# LM22674-5_0.net
KiCad netlist of a schematic drawn in EAGLE
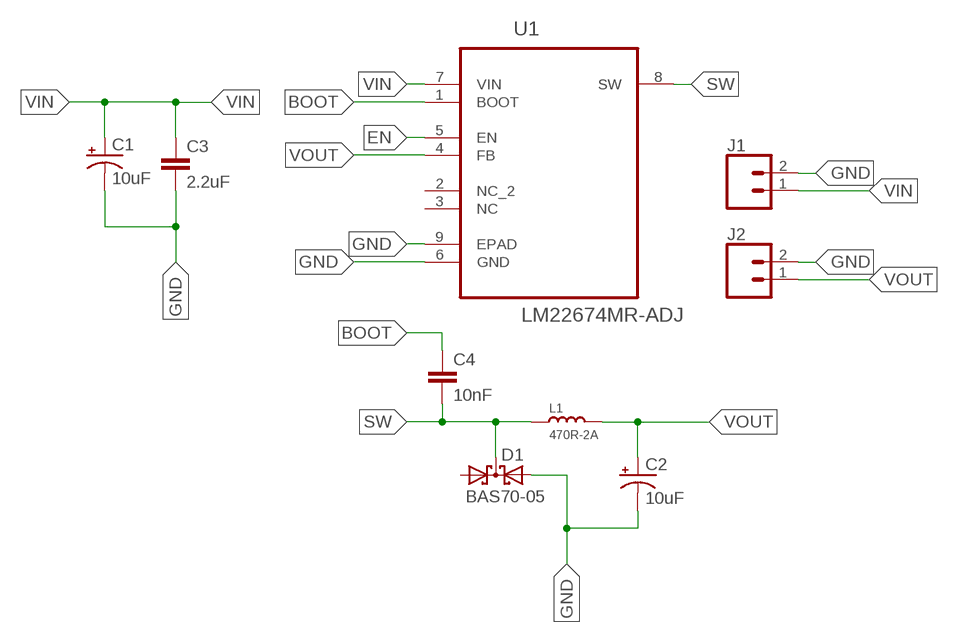
[diagram p0: schematic, sheet 1]

(export (version "E")
  (design (tool "Eeschema 10.0.6"))
  (components
    (comp (ref "C1")
      (value "10uF")
      (footprint "eagle-import:EIA3216")
      (libsource (lib "eagle-import") (part "10UF-POLAR-EIA3216-16V-10%(TANT)"))
    )
    (comp (ref "C2")
      (value "10uF")
      (footprint "eagle-import:EIA3216")
      (libsource (lib "eagle-import") (part "10UF-POLAR-EIA3216-16V-10%(TANT)"))
    )
    (comp (ref "C3")
      (value "2.2uF")
      (footprint "eagle-import:0603")
      (libsource (lib "eagle-import") (part "2.2UF-0603-10V-20%"))
    )
    (comp (ref "C4")
      (value "10nF")
      (footprint "eagle-import:0603")
      (libsource (lib "eagle-import") (part "10NF-0603-50V-10%"))
    )
    (comp (ref "D1")
      (value "BAS70-05")
      (footprint "eagle-import:SOT23")
      (libsource (lib "eagle-import") (part "BAS70-05"))
    )
    (comp (ref "J1")
      (value "CONN_02PTH4")
      (footprint "eagle-import:1X02_XTRA_BIG")
      (libsource (lib "eagle-import") (part "CONN_02PTH4"))
    )
    (comp (ref "J2")
      (value "CONN_02PTH4")
      (footprint "eagle-import:1X02_XTRA_BIG")
      (libsource (lib "eagle-import") (part "CONN_02PTH4"))
    )
    (comp (ref "L1")
      (value "470R-2A")
      (footprint "eagle-import:L0805")
      (fields (field (name "MPN") "WLB2012-471T20"))
      (libsource (lib "eagle-import") (part "SMD-FERRITE-BEAD-470R-2A(0805)'0805'"))
    )
    (comp (ref "U1")
      (value "LM22674MR-ADJ")
      (footprint "eagle-import:SOIC127P600X168-9N")
      (fields (field (name "MF") "Texas Instruments"))
      (libsource (lib "eagle-import") (part "LM22674MR-ADJ"))
    )
  )
  (nets
    (net (code "1") (name "BOOT") (class "Default")
      (node (ref "C4") (pin "1") (pinfunction "1_1") (pintype "passive"))
      (node (ref "U1") (pin "1") (pinfunction "BOOT_1") (pintype "power_in"))
    )
    (net (code "2") (name "EN") (class "Default")
      (node (ref "U1") (pin "5") (pinfunction "EN_5") (pintype "input"))
    )
    (net (code "3") (name "GND") (class "Default")
      (node (ref "C1") (pin "-") (pinfunction "-_-") (pintype "passive"))
      (node (ref "C2") (pin "-") (pinfunction "-_-") (pintype "passive"))
      (node (ref "C3") (pin "2") (pinfunction "2_2") (pintype "passive"))
      (node (ref "D1") (pin "2") (pinfunction "A2_2") (pintype "passive"))
      (node (ref "J1") (pin "2") (pinfunction "2_2") (pintype "passive"))
      (node (ref "J2") (pin "2") (pinfunction "2_2") (pintype "passive"))
      (node (ref "U1") (pin "6") (pinfunction "GND_6") (pintype "passive"))
      (node (ref "U1") (pin "9") (pinfunction "EPAD_9") (pintype "passive"))
    )
    (net (code "4") (name "SW") (class "Default")
      (node (ref "C4") (pin "2") (pinfunction "2_2") (pintype "passive"))
      (node (ref "D1") (pin "3") (pinfunction "C_3") (pintype "passive"))
      (node (ref "L1") (pin "1") (pinfunction "1_1") (pintype "passive"))
      (node (ref "U1") (pin "8") (pinfunction "SW_8") (pintype "output"))
    )
    (net (code "5") (name "VIN") (class "Default")
      (node (ref "C1") (pin "+") (pinfunction "+_+") (pintype "passive"))
      (node (ref "C3") (pin "1") (pinfunction "1_1") (pintype "passive"))
      (node (ref "J1") (pin "1") (pinfunction "1_1") (pintype "passive"))
      (node (ref "U1") (pin "7") (pinfunction "VIN_7") (pintype "power_in"))
    )
    (net (code "6") (name "VOUT") (class "Default")
      (node (ref "C2") (pin "+") (pinfunction "+_+") (pintype "passive"))
      (node (ref "J2") (pin "1") (pinfunction "1_1") (pintype "passive"))
      (node (ref "L1") (pin "2") (pinfunction "2_2") (pintype "passive"))
      (node (ref "U1") (pin "4") (pinfunction "FB_4") (pintype "input"))
    )
    (net (code "7") (name "unconnected-(D1-A1-Pad1)") (class "Default")
      (node (ref "D1") (pin "1") (pinfunction "A1_1") (pintype "passive"))
    )
    (net (code "8") (name "unconnected-(U1-NC-Pad3)") (class "Default")
      (node (ref "U1") (pin "3") (pinfunction "NC_3") (pintype "no_connect"))
    )
    (net (code "9") (name "unconnected-(U1-NC_2-Pad2)") (class "Default")
      (node (ref "U1") (pin "2") (pinfunction "NC_2_2") (pintype "no_connect"))
    )
  )
)
